# H19R1_Frontend_2.net
KiCad netlist of a schematic drawn in Altium Designer
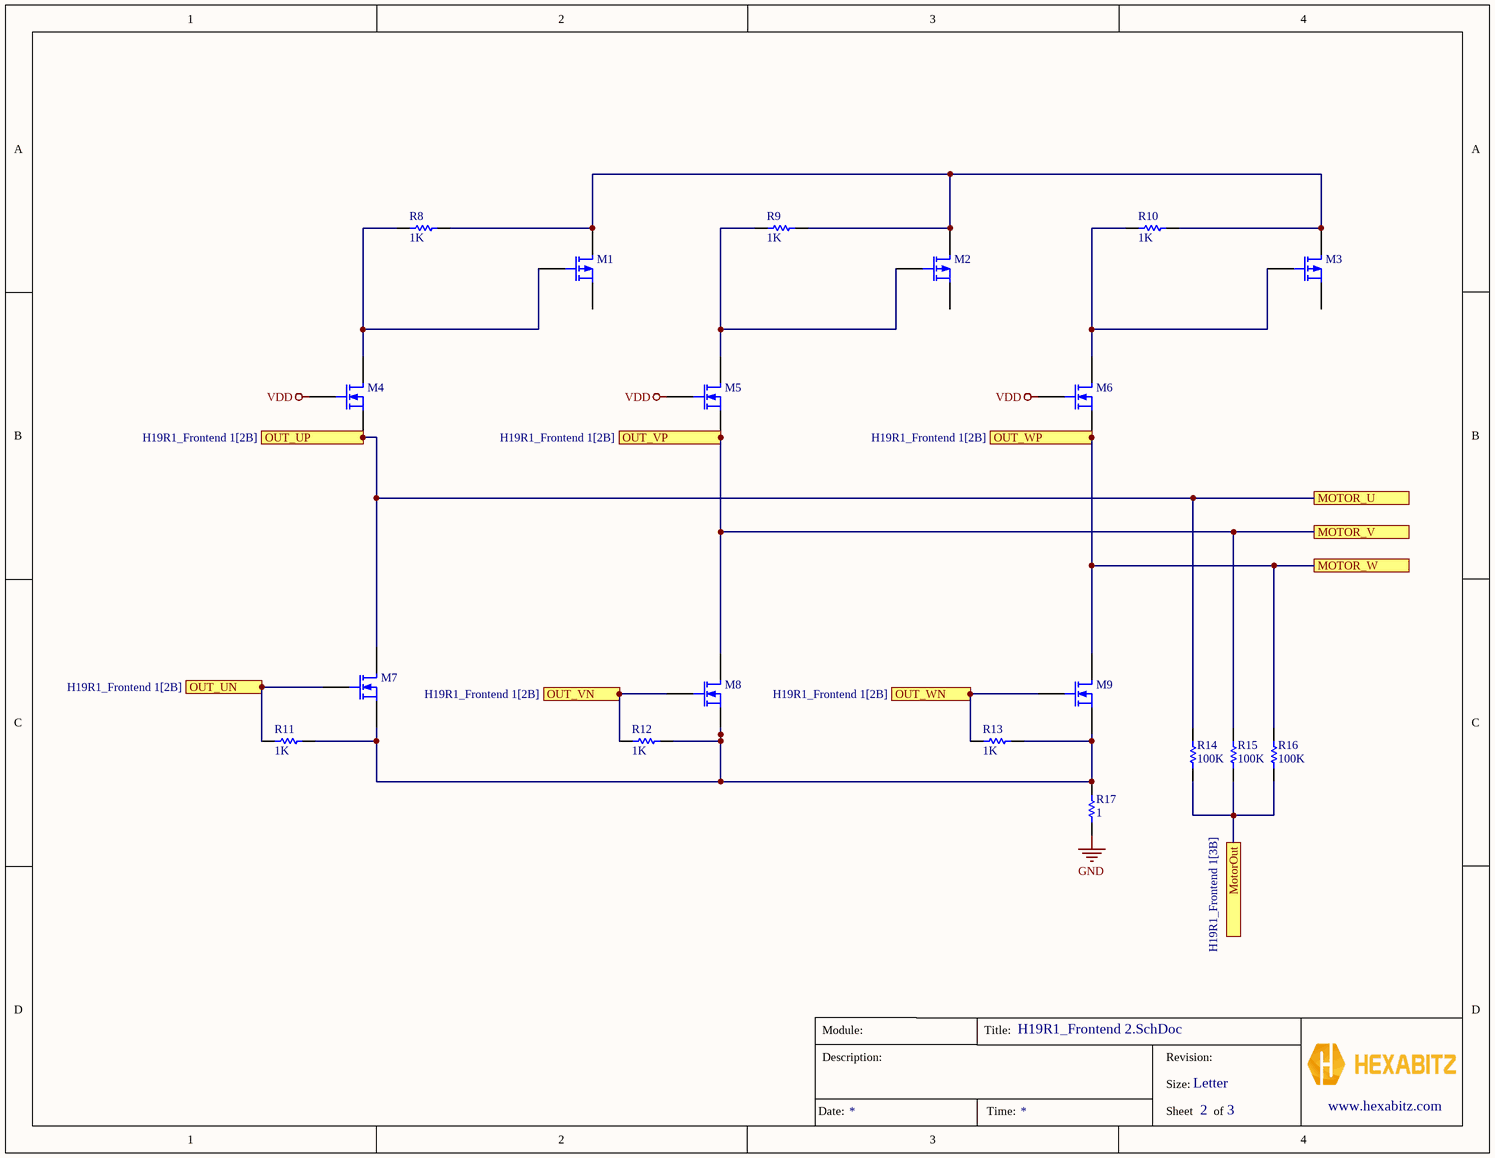
[diagram p0: H19R1_Frontend 2.SchDoc]

(export (version "E")
  (design (tool "Eeschema 10.0.6"))
  (components
    (comp (ref "M1")
      (value "P-channel Power MOSFET VDMOS Model")
      (libsource (lib "Simulation Generic Components") (part "MOSFET P-ch VDMOS"))
    )
    (comp (ref "M2")
      (value "P-channel Power MOSFET VDMOS Model")
      (libsource (lib "Simulation Generic Components") (part "MOSFET P-ch VDMOS"))
    )
    (comp (ref "M3")
      (value "P-channel Power MOSFET VDMOS Model")
      (libsource (lib "Simulation Generic Components") (part "MOSFET P-ch VDMOS"))
    )
    (comp (ref "M4")
      (value "N-channel Power MOSFET VDMOS Model")
      (libsource (lib "Simulation Generic Components") (part "MOSFET N-ch VDMOS"))
    )
    (comp (ref "M5")
      (value "N-channel Power MOSFET VDMOS Model")
      (libsource (lib "Simulation Generic Components") (part "MOSFET N-ch VDMOS"))
    )
    (comp (ref "M6")
      (value "N-channel Power MOSFET VDMOS Model")
      (libsource (lib "Simulation Generic Components") (part "MOSFET N-ch VDMOS"))
    )
    (comp (ref "M7")
      (value "N-channel Power MOSFET VDMOS Model")
      (libsource (lib "Simulation Generic Components") (part "MOSFET N-ch VDMOS"))
    )
    (comp (ref "M8")
      (value "N-channel Power MOSFET VDMOS Model")
      (libsource (lib "Simulation Generic Components") (part "MOSFET N-ch VDMOS"))
    )
    (comp (ref "M9")
      (value "N-channel Power MOSFET VDMOS Model")
      (libsource (lib "Simulation Generic Components") (part "MOSFET N-ch VDMOS"))
    )
    (comp (ref "R8")
      (value "1K")
      (description "Resistor")
      (libsource (lib "Simulation Generic Components") (part "Resistor"))
    )
    (comp (ref "R9")
      (value "1K")
      (description "Resistor")
      (libsource (lib "Simulation Generic Components") (part "Resistor"))
    )
    (comp (ref "R10")
      (value "1K")
      (description "Resistor")
      (libsource (lib "Simulation Generic Components") (part "Resistor"))
    )
    (comp (ref "R11")
      (value "1K")
      (description "Resistor")
      (libsource (lib "Simulation Generic Components") (part "Resistor"))
    )
    (comp (ref "R12")
      (value "1K")
      (description "Resistor")
      (libsource (lib "Simulation Generic Components") (part "Resistor"))
    )
    (comp (ref "R13")
      (value "1K")
      (description "Resistor")
      (libsource (lib "Simulation Generic Components") (part "Resistor"))
    )
    (comp (ref "R14")
      (value "100K")
      (description "Resistor")
      (libsource (lib "Simulation Generic Components") (part "Resistor"))
    )
    (comp (ref "R15")
      (value "100K")
      (description "Resistor")
      (libsource (lib "Simulation Generic Components") (part "Resistor"))
    )
    (comp (ref "R16")
      (value "100K")
      (description "Resistor")
      (libsource (lib "Simulation Generic Components") (part "Resistor"))
    )
    (comp (ref "R17")
      (value "1")
      (description "Resistor")
      (libsource (lib "Simulation Generic Components") (part "Resistor"))
    )
  )
  (nets
    (net (code "1") (name "/MOTOR_U") (class "Default")
      (node (ref "M4") (pin "3") (pinfunction "S_3") (pintype "passive"))
      (node (ref "M7") (pin "1") (pinfunction "D_1") (pintype "passive"))
      (node (ref "R14") (pin "2") (pinfunction "2_2") (pintype "passive"))
    )
    (net (code "2") (name "/MOTOR_V") (class "Default")
      (node (ref "M5") (pin "3") (pinfunction "S_3") (pintype "passive"))
      (node (ref "M8") (pin "1") (pinfunction "D_1") (pintype "passive"))
      (node (ref "R15") (pin "2") (pinfunction "2_2") (pintype "passive"))
    )
    (net (code "3") (name "/MOTOR_W") (class "Default")
      (node (ref "M6") (pin "3") (pinfunction "S_3") (pintype "passive"))
      (node (ref "M9") (pin "1") (pinfunction "D_1") (pintype "passive"))
      (node (ref "R16") (pin "2") (pinfunction "2_2") (pintype "passive"))
    )
    (net (code "4") (name "/MotorOut") (class "Default")
      (node (ref "R14") (pin "1") (pinfunction "1_1") (pintype "passive"))
      (node (ref "R15") (pin "1") (pinfunction "1_1") (pintype "passive"))
      (node (ref "R16") (pin "1") (pinfunction "1_1") (pintype "passive"))
    )
    (net (code "5") (name "/OUT_UN") (class "Default")
      (node (ref "M7") (pin "2") (pinfunction "G_2") (pintype "passive"))
      (node (ref "R11") (pin "1") (pinfunction "1_1") (pintype "passive"))
    )
    (net (code "6") (name "/OUT_VN") (class "Default")
      (node (ref "M8") (pin "2") (pinfunction "G_2") (pintype "passive"))
      (node (ref "R12") (pin "1") (pinfunction "1_1") (pintype "passive"))
    )
    (net (code "7") (name "/OUT_WN") (class "Default")
      (node (ref "M9") (pin "2") (pinfunction "G_2") (pintype "passive"))
      (node (ref "R13") (pin "1") (pinfunction "1_1") (pintype "passive"))
    )
    (net (code "8") (name "GND") (class "Default")
      (node (ref "R17") (pin "1") (pinfunction "1_1") (pintype "passive"))
    )
    (net (code "9") (name "Net-(M1-D)") (class "Default")
      (node (ref "M1") (pin "1") (pinfunction "D_1") (pintype "passive"))
      (node (ref "M2") (pin "1") (pinfunction "D_1") (pintype "passive"))
      (node (ref "M3") (pin "1") (pinfunction "D_1") (pintype "passive"))
      (node (ref "R10") (pin "2") (pinfunction "2_2") (pintype "passive"))
      (node (ref "R8") (pin "2") (pinfunction "2_2") (pintype "passive"))
      (node (ref "R9") (pin "2") (pinfunction "2_2") (pintype "passive"))
    )
    (net (code "10") (name "Net-(M1-G)") (class "Default")
      (node (ref "M1") (pin "2") (pinfunction "G_2") (pintype "passive"))
      (node (ref "M4") (pin "1") (pinfunction "D_1") (pintype "passive"))
      (node (ref "R8") (pin "1") (pinfunction "1_1") (pintype "passive"))
    )
    (net (code "11") (name "Net-(M2-G)") (class "Default")
      (node (ref "M2") (pin "2") (pinfunction "G_2") (pintype "passive"))
      (node (ref "M5") (pin "1") (pinfunction "D_1") (pintype "passive"))
      (node (ref "R9") (pin "1") (pinfunction "1_1") (pintype "passive"))
    )
    (net (code "12") (name "Net-(M3-G)") (class "Default")
      (node (ref "M3") (pin "2") (pinfunction "G_2") (pintype "passive"))
      (node (ref "M6") (pin "1") (pinfunction "D_1") (pintype "passive"))
      (node (ref "R10") (pin "1") (pinfunction "1_1") (pintype "passive"))
    )
    (net (code "13") (name "Net-(M7-S)") (class "Default")
      (node (ref "M7") (pin "3") (pinfunction "S_3") (pintype "passive"))
      (node (ref "M8") (pin "3") (pinfunction "S_3") (pintype "passive"))
      (node (ref "M9") (pin "3") (pinfunction "S_3") (pintype "passive"))
      (node (ref "R11") (pin "2") (pinfunction "2_2") (pintype "passive"))
      (node (ref "R12") (pin "2") (pinfunction "2_2") (pintype "passive"))
      (node (ref "R13") (pin "2") (pinfunction "2_2") (pintype "passive"))
      (node (ref "R17") (pin "2") (pinfunction "2_2") (pintype "passive"))
    )
    (net (code "14") (name "VDD") (class "Default")
      (node (ref "M4") (pin "2") (pinfunction "G_2") (pintype "passive"))
      (node (ref "M5") (pin "2") (pinfunction "G_2") (pintype "passive"))
      (node (ref "M6") (pin "2") (pinfunction "G_2") (pintype "passive"))
    )
    (net (code "15") (name "unconnected-(M1-S-Pad3)") (class "Default")
      (node (ref "M1") (pin "3") (pinfunction "S_3") (pintype "passive"))
    )
    (net (code "16") (name "unconnected-(M2-S-Pad3)") (class "Default")
      (node (ref "M2") (pin "3") (pinfunction "S_3") (pintype "passive"))
    )
    (net (code "17") (name "unconnected-(M3-S-Pad3)") (class "Default")
      (node (ref "M3") (pin "3") (pinfunction "S_3") (pintype "passive"))
    )
  )
)
